# clock.net
KiCad netlist of a schematic drawn in EAGLE
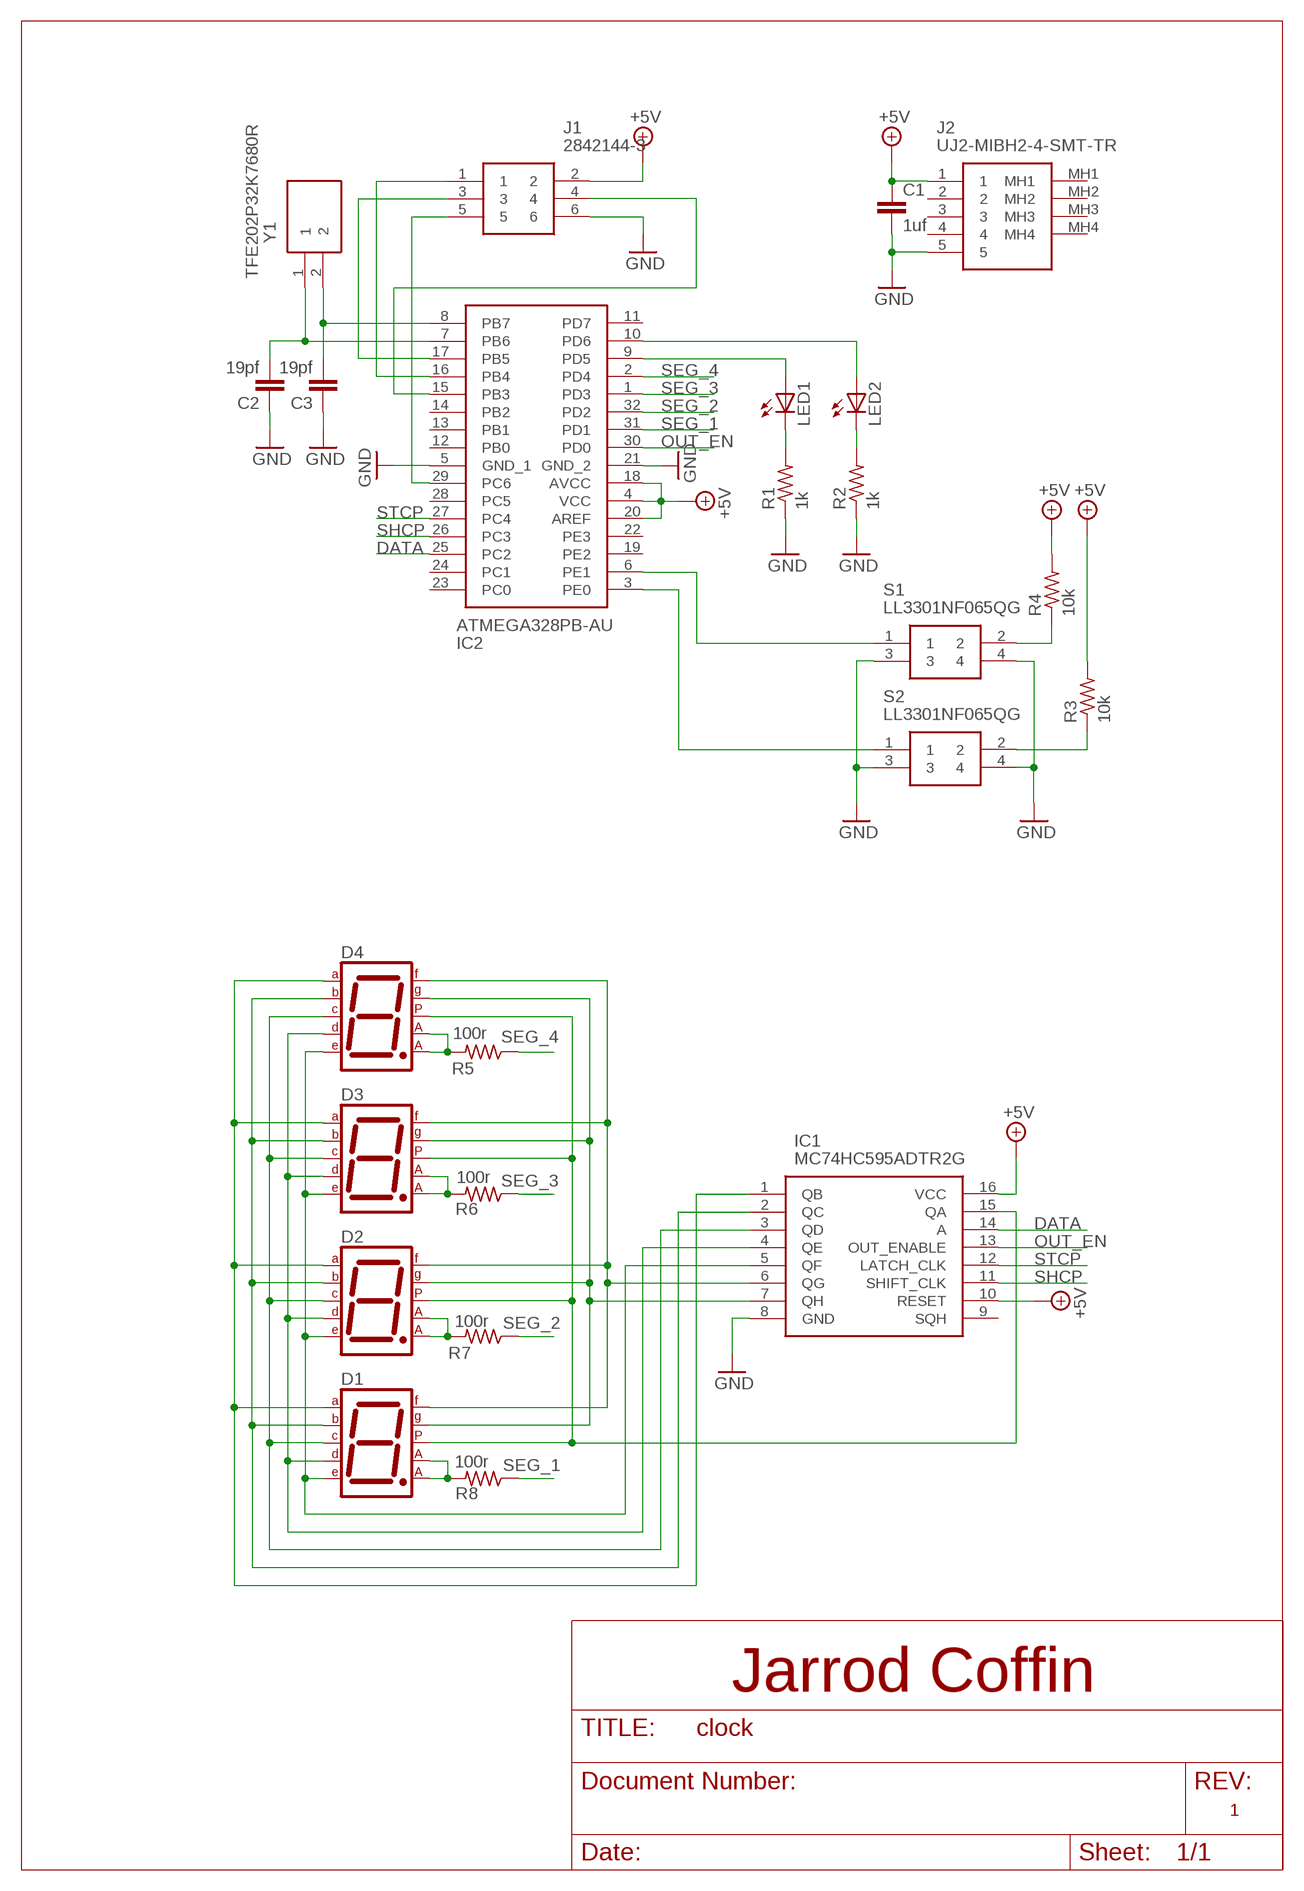
[diagram p0: schematic, sheet 1]

(export (version "E")
  (design (tool "Eeschema 10.0.6"))
  (components
    (comp (ref "C1")
      (value "1uf")
      (footprint "eagle-import:C0805")
      (libsource (lib "eagle-import") (part "C-EUC0805"))
    )
    (comp (ref "C2")
      (value "19pf")
      (footprint "eagle-import:C0603")
      (libsource (lib "eagle-import") (part "C-EUC0603"))
    )
    (comp (ref "C3")
      (value "19pf")
      (footprint "eagle-import:C0603")
      (libsource (lib "eagle-import") (part "C-EUC0603"))
    )
    (comp (ref "D1")
      (value "7SEG-CA")
      (footprint "eagle-import:7SEG-13")
      (libsource (lib "eagle-import") (part "7SEG-CA"))
    )
    (comp (ref "D2")
      (value "7SEG-CA")
      (footprint "eagle-import:7SEG-13")
      (libsource (lib "eagle-import") (part "7SEG-CA"))
    )
    (comp (ref "D3")
      (value "7SEG-CA")
      (footprint "eagle-import:7SEG-13")
      (libsource (lib "eagle-import") (part "7SEG-CA"))
    )
    (comp (ref "D4")
      (value "7SEG-CA")
      (footprint "eagle-import:7SEG-13")
      (libsource (lib "eagle-import") (part "7SEG-CA"))
    )
    (comp (ref "IC1")
      (value "MC74HC595ADTR2G")
      (footprint "eagle-import:SOP65P640X120-16N")
      (fields (field (name "MOUSER_PART_NUMBER") "863-MC74HC595ADTR2G"))
      (libsource (lib "eagle-import") (part "MC74HC595ADTR2G"))
    )
    (comp (ref "IC2")
      (value "ATMEGA328PB-AU")
      (footprint "eagle-import:QFP80P900X900X120-32N")
      (fields (field (name "MOUSER_PART_NUMBER") "556-ATMEGA328PB-AU"))
      (libsource (lib "eagle-import") (part "ATMEGA328PB-AU"))
    )
    (comp (ref "J1")
      (value "2842144-3")
      (footprint "eagle-import:HUSSP6W50P200_2X3_600X400X590P")
      (fields (field (name "MOUSER_PART_NUMBER") "571-2842144-3"))
      (libsource (lib "eagle-import") (part "2842144-3"))
    )
    (comp (ref "J2")
      (value "UJ2-MIBH2-4-SMT-TR")
      (footprint "eagle-import:UJ2MIBH24SMTTR")
      (fields (field (name "MOUSER_PART_NUMBER") "490-UJ2-MIBH2-4-SMT"))
      (libsource (lib "eagle-import") (part "UJ2-MIBH2-4-SMT-TR"))
    )
    (comp (ref "LED1")
      (value "LED3MM")
      (footprint "eagle-import:LED3MM")
      (libsource (lib "eagle-import") (part "LED3MM"))
    )
    (comp (ref "LED2")
      (value "LED3MM")
      (footprint "eagle-import:LED3MM")
      (libsource (lib "eagle-import") (part "LED3MM"))
    )
    (comp (ref "R1")
      (value "1k")
      (footprint "eagle-import:R0805")
      (libsource (lib "eagle-import") (part "R-US_R0805"))
    )
    (comp (ref "R2")
      (value "1k")
      (footprint "eagle-import:R0805")
      (libsource (lib "eagle-import") (part "R-US_R0805"))
    )
    (comp (ref "R3")
      (value "10k")
      (footprint "eagle-import:R0805")
      (libsource (lib "eagle-import") (part "R-US_R0805"))
    )
    (comp (ref "R4")
      (value "10k")
      (footprint "eagle-import:R0805")
      (libsource (lib "eagle-import") (part "R-US_R0805"))
    )
    (comp (ref "R5")
      (value "100r")
      (footprint "eagle-import:R0805")
      (libsource (lib "eagle-import") (part "R-US_R0805"))
    )
    (comp (ref "R6")
      (value "100r")
      (footprint "eagle-import:R0805")
      (libsource (lib "eagle-import") (part "R-US_R0805"))
    )
    (comp (ref "R7")
      (value "100r")
      (footprint "eagle-import:R0805")
      (libsource (lib "eagle-import") (part "R-US_R0805"))
    )
    (comp (ref "R8")
      (value "100r")
      (footprint "eagle-import:R0805")
      (libsource (lib "eagle-import") (part "R-US_R0805"))
    )
    (comp (ref "S1")
      (value "LL3301NF065QG")
      (footprint "eagle-import:LL3301NF065QG")
      (fields (field (name "MOUSER_PART_NUMBER") "612-LL3301NF065QG"))
      (libsource (lib "eagle-import") (part "LL3301NF065QG"))
    )
    (comp (ref "S2")
      (value "LL3301NF065QG")
      (footprint "eagle-import:LL3301NF065QG")
      (fields (field (name "MOUSER_PART_NUMBER") "612-LL3301NF065QG"))
      (libsource (lib "eagle-import") (part "LL3301NF065QG"))
    )
    (comp (ref "Y1")
      (value "TFE202P32K7680R")
      (footprint "eagle-import:TFE202P32K7680R")
      (fields (field (name "MOUSER_PART_NUMBER") "774-TFE202P32K7680R"))
      (libsource (lib "eagle-import") (part "TFE202P32K7680R"))
    )
  )
  (nets
    (net (code "1") (name "+5V") (class "Default")
      (node (ref "C1") (pin "1") (pinfunction "1_1") (pintype "passive"))
      (node (ref "IC1") (pin "10") (pinfunction "RESET_10") (pintype "bidirectional"))
      (node (ref "IC1") (pin "16") (pinfunction "VCC_16") (pintype "power_in"))
      (node (ref "IC2") (pin "18") (pinfunction "AVCC_18") (pintype "bidirectional"))
      (node (ref "IC2") (pin "20") (pinfunction "AREF_20") (pintype "bidirectional"))
      (node (ref "IC2") (pin "4") (pinfunction "VCC_4") (pintype "bidirectional"))
      (node (ref "J1") (pin "2") (pinfunction "2_2") (pintype "bidirectional"))
      (node (ref "J2") (pin "1") (pinfunction "1_1") (pintype "bidirectional"))
      (node (ref "R3") (pin "2") (pinfunction "2_2") (pintype "passive"))
      (node (ref "R4") (pin "2") (pinfunction "2_2") (pintype "passive"))
    )
    (net (code "2") (name "/DATA") (class "Default")
      (node (ref "IC1") (pin "14") (pinfunction "A_14") (pintype "bidirectional"))
      (node (ref "IC2") (pin "25") (pinfunction "PC2_25") (pintype "bidirectional"))
    )
    (net (code "3") (name "/OUT_EN") (class "Default")
      (node (ref "IC1") (pin "13") (pinfunction "OUT_ENABLE_13") (pintype "output"))
      (node (ref "IC2") (pin "30") (pinfunction "PD0_30") (pintype "bidirectional"))
    )
    (net (code "4") (name "/SEG_1") (class "Default")
      (node (ref "IC2") (pin "31") (pinfunction "PD1_31") (pintype "bidirectional"))
      (node (ref "R8") (pin "1") (pinfunction "1_1") (pintype "passive"))
    )
    (net (code "5") (name "/SEG_2") (class "Default")
      (node (ref "IC2") (pin "32") (pinfunction "PD2_32") (pintype "bidirectional"))
      (node (ref "R7") (pin "1") (pinfunction "1_1") (pintype "passive"))
    )
    (net (code "6") (name "/SEG_3") (class "Default")
      (node (ref "IC2") (pin "1") (pinfunction "PD3_1") (pintype "bidirectional"))
      (node (ref "R6") (pin "1") (pinfunction "1_1") (pintype "passive"))
    )
    (net (code "7") (name "/SEG_4") (class "Default")
      (node (ref "IC2") (pin "2") (pinfunction "PD4_2") (pintype "bidirectional"))
      (node (ref "R5") (pin "1") (pinfunction "1_1") (pintype "passive"))
    )
    (net (code "8") (name "/SHCP") (class "Default")
      (node (ref "IC1") (pin "11") (pinfunction "SHIFT_CLK_11") (pintype "input"))
      (node (ref "IC2") (pin "26") (pinfunction "PC3_26") (pintype "bidirectional"))
    )
    (net (code "9") (name "/STCP") (class "Default")
      (node (ref "IC1") (pin "12") (pinfunction "LATCH_CLK_12") (pintype "input"))
      (node (ref "IC2") (pin "27") (pinfunction "PC4_27") (pintype "bidirectional"))
    )
    (net (code "10") (name "GND") (class "Default")
      (node (ref "C1") (pin "2") (pinfunction "2_2") (pintype "passive"))
      (node (ref "C2") (pin "1") (pinfunction "1_1") (pintype "passive"))
      (node (ref "C3") (pin "1") (pinfunction "1_1") (pintype "passive"))
      (node (ref "IC1") (pin "8") (pinfunction "GND_8") (pintype "power_in"))
      (node (ref "IC2") (pin "21") (pinfunction "GND_2_21") (pintype "bidirectional"))
      (node (ref "IC2") (pin "5") (pinfunction "GND_1_5") (pintype "bidirectional"))
      (node (ref "J1") (pin "6") (pinfunction "6_6") (pintype "bidirectional"))
      (node (ref "J2") (pin "5") (pinfunction "5_5") (pintype "bidirectional"))
      (node (ref "R1") (pin "1") (pinfunction "1_1") (pintype "passive"))
      (node (ref "R2") (pin "1") (pinfunction "1_1") (pintype "passive"))
      (node (ref "S1") (pin "3") (pinfunction "3_3") (pintype "bidirectional"))
      (node (ref "S1") (pin "4") (pinfunction "4_4") (pintype "bidirectional"))
      (node (ref "S2") (pin "3") (pinfunction "3_3") (pintype "bidirectional"))
      (node (ref "S2") (pin "4") (pinfunction "4_4") (pintype "bidirectional"))
    )
    (net (code "11") (name "Net-(D1-A)") (class "Default")
      (node (ref "D1") (pin "7") (pinfunction "A_7") (pintype "passive"))
      (node (ref "D2") (pin "7") (pinfunction "A_7") (pintype "passive"))
      (node (ref "D3") (pin "7") (pinfunction "A_7") (pintype "passive"))
      (node (ref "D4") (pin "7") (pinfunction "A_7") (pintype "passive"))
      (node (ref "IC1") (pin "1") (pinfunction "QB_1") (pintype "bidirectional"))
    )
    (net (code "12") (name "Net-(D1-B)") (class "Default")
      (node (ref "D1") (pin "6") (pinfunction "B_6") (pintype "passive"))
      (node (ref "D2") (pin "6") (pinfunction "B_6") (pintype "passive"))
      (node (ref "D3") (pin "6") (pinfunction "B_6") (pintype "passive"))
      (node (ref "D4") (pin "6") (pinfunction "B_6") (pintype "passive"))
      (node (ref "IC1") (pin "2") (pinfunction "QC_2") (pintype "bidirectional"))
    )
    (net (code "13") (name "Net-(D1-C)") (class "Default")
      (node (ref "D1") (pin "4") (pinfunction "C_4") (pintype "passive"))
      (node (ref "D2") (pin "4") (pinfunction "C_4") (pintype "passive"))
      (node (ref "D3") (pin "4") (pinfunction "C_4") (pintype "passive"))
      (node (ref "D4") (pin "4") (pinfunction "C_4") (pintype "passive"))
      (node (ref "IC1") (pin "3") (pinfunction "QD_3") (pintype "bidirectional"))
    )
    (net (code "14") (name "Net-(D1-CA1)") (class "Default")
      (node (ref "D1") (pin "3") (pinfunction "CA1_3") (pintype "passive"))
      (node (ref "D1") (pin "8") (pinfunction "CA2_8") (pintype "passive"))
      (node (ref "R8") (pin "2") (pinfunction "2_2") (pintype "passive"))
    )
    (net (code "15") (name "Net-(D1-D)") (class "Default")
      (node (ref "D1") (pin "2") (pinfunction "D_2") (pintype "passive"))
      (node (ref "D2") (pin "2") (pinfunction "D_2") (pintype "passive"))
      (node (ref "D3") (pin "2") (pinfunction "D_2") (pintype "passive"))
      (node (ref "D4") (pin "2") (pinfunction "D_2") (pintype "passive"))
      (node (ref "IC1") (pin "4") (pinfunction "QE_4") (pintype "bidirectional"))
    )
    (net (code "16") (name "Net-(D1-DP)") (class "Default")
      (node (ref "D1") (pin "5") (pinfunction "DP_5") (pintype "passive"))
      (node (ref "D2") (pin "5") (pinfunction "DP_5") (pintype "passive"))
      (node (ref "D3") (pin "5") (pinfunction "DP_5") (pintype "passive"))
      (node (ref "D4") (pin "5") (pinfunction "DP_5") (pintype "passive"))
      (node (ref "IC1") (pin "15") (pinfunction "QA_15") (pintype "bidirectional"))
    )
    (net (code "17") (name "Net-(D1-E)") (class "Default")
      (node (ref "D1") (pin "1") (pinfunction "E_1") (pintype "passive"))
      (node (ref "D2") (pin "1") (pinfunction "E_1") (pintype "passive"))
      (node (ref "D3") (pin "1") (pinfunction "E_1") (pintype "passive"))
      (node (ref "D4") (pin "1") (pinfunction "E_1") (pintype "passive"))
      (node (ref "IC1") (pin "5") (pinfunction "QF_5") (pintype "bidirectional"))
    )
    (net (code "18") (name "Net-(D1-F)") (class "Default")
      (node (ref "D1") (pin "9") (pinfunction "F_9") (pintype "passive"))
      (node (ref "D2") (pin "9") (pinfunction "F_9") (pintype "passive"))
      (node (ref "D3") (pin "9") (pinfunction "F_9") (pintype "passive"))
      (node (ref "D4") (pin "9") (pinfunction "F_9") (pintype "passive"))
      (node (ref "IC1") (pin "6") (pinfunction "QG_6") (pintype "bidirectional"))
    )
    (net (code "19") (name "Net-(D1-G)") (class "Default")
      (node (ref "D1") (pin "10") (pinfunction "G_10") (pintype "passive"))
      (node (ref "D2") (pin "10") (pinfunction "G_10") (pintype "passive"))
      (node (ref "D3") (pin "10") (pinfunction "G_10") (pintype "passive"))
      (node (ref "D4") (pin "10") (pinfunction "G_10") (pintype "passive"))
      (node (ref "IC1") (pin "7") (pinfunction "QH_7") (pintype "bidirectional"))
    )
    (net (code "20") (name "Net-(D2-CA1)") (class "Default")
      (node (ref "D2") (pin "3") (pinfunction "CA1_3") (pintype "passive"))
      (node (ref "D2") (pin "8") (pinfunction "CA2_8") (pintype "passive"))
      (node (ref "R7") (pin "2") (pinfunction "2_2") (pintype "passive"))
    )
    (net (code "21") (name "Net-(D3-CA1)") (class "Default")
      (node (ref "D3") (pin "3") (pinfunction "CA1_3") (pintype "passive"))
      (node (ref "D3") (pin "8") (pinfunction "CA2_8") (pintype "passive"))
      (node (ref "R6") (pin "2") (pinfunction "2_2") (pintype "passive"))
    )
    (net (code "22") (name "Net-(D4-CA1)") (class "Default")
      (node (ref "D4") (pin "3") (pinfunction "CA1_3") (pintype "passive"))
      (node (ref "D4") (pin "8") (pinfunction "CA2_8") (pintype "passive"))
      (node (ref "R5") (pin "2") (pinfunction "2_2") (pintype "passive"))
    )
    (net (code "23") (name "Net-(IC2-PB3)") (class "Default")
      (node (ref "IC2") (pin "15") (pinfunction "PB3_15") (pintype "bidirectional"))
      (node (ref "J1") (pin "4") (pinfunction "4_4") (pintype "bidirectional"))
    )
    (net (code "24") (name "Net-(IC2-PB4)") (class "Default")
      (node (ref "IC2") (pin "16") (pinfunction "PB4_16") (pintype "bidirectional"))
      (node (ref "J1") (pin "1") (pinfunction "1_1") (pintype "bidirectional"))
    )
    (net (code "25") (name "Net-(IC2-PB5)") (class "Default")
      (node (ref "IC2") (pin "17") (pinfunction "PB5_17") (pintype "bidirectional"))
      (node (ref "J1") (pin "3") (pinfunction "3_3") (pintype "bidirectional"))
    )
    (net (code "26") (name "Net-(IC2-PB6)") (class "Default")
      (node (ref "C2") (pin "2") (pinfunction "2_2") (pintype "passive"))
      (node (ref "IC2") (pin "7") (pinfunction "PB6_7") (pintype "bidirectional"))
      (node (ref "Y1") (pin "1") (pinfunction "1_1") (pintype "bidirectional"))
    )
    (net (code "27") (name "Net-(IC2-PB7)") (class "Default")
      (node (ref "C3") (pin "2") (pinfunction "2_2") (pintype "passive"))
      (node (ref "IC2") (pin "8") (pinfunction "PB7_8") (pintype "bidirectional"))
      (node (ref "Y1") (pin "2") (pinfunction "2_2") (pintype "bidirectional"))
    )
    (net (code "28") (name "Net-(IC2-PC6)") (class "Default")
      (node (ref "IC2") (pin "29") (pinfunction "PC6_29") (pintype "bidirectional"))
      (node (ref "J1") (pin "5") (pinfunction "5_5") (pintype "bidirectional"))
    )
    (net (code "29") (name "Net-(IC2-PD5)") (class "Default")
      (node (ref "IC2") (pin "9") (pinfunction "PD5_9") (pintype "bidirectional"))
      (node (ref "LED1") (pin "A") (pinfunction "A_A") (pintype "passive"))
    )
    (net (code "30") (name "Net-(IC2-PD6)") (class "Default")
      (node (ref "IC2") (pin "10") (pinfunction "PD6_10") (pintype "bidirectional"))
      (node (ref "LED2") (pin "A") (pinfunction "A_A") (pintype "passive"))
    )
    (net (code "31") (name "Net-(IC2-PE0)") (class "Default")
      (node (ref "IC2") (pin "3") (pinfunction "PE0_3") (pintype "bidirectional"))
      (node (ref "S2") (pin "1") (pinfunction "1_1") (pintype "bidirectional"))
    )
    (net (code "32") (name "Net-(IC2-PE1)") (class "Default")
      (node (ref "IC2") (pin "6") (pinfunction "PE1_6") (pintype "bidirectional"))
      (node (ref "S1") (pin "1") (pinfunction "1_1") (pintype "bidirectional"))
    )
    (net (code "33") (name "Net-(LED1-C)") (class "Default")
      (node (ref "LED1") (pin "K") (pinfunction "C_K") (pintype "passive"))
      (node (ref "R1") (pin "2") (pinfunction "2_2") (pintype "passive"))
    )
    (net (code "34") (name "Net-(LED2-C)") (class "Default")
      (node (ref "LED2") (pin "K") (pinfunction "C_K") (pintype "passive"))
      (node (ref "R2") (pin "2") (pinfunction "2_2") (pintype "passive"))
    )
    (net (code "35") (name "Net-(R3-Pad1)") (class "Default")
      (node (ref "R3") (pin "1") (pinfunction "1_1") (pintype "passive"))
      (node (ref "S2") (pin "2") (pinfunction "2_2") (pintype "bidirectional"))
    )
    (net (code "36") (name "Net-(R4-Pad1)") (class "Default")
      (node (ref "R4") (pin "1") (pinfunction "1_1") (pintype "passive"))
      (node (ref "S1") (pin "2") (pinfunction "2_2") (pintype "bidirectional"))
    )
    (net (code "37") (name "unconnected-(IC1-SQH-Pad9)") (class "Default")
      (node (ref "IC1") (pin "9") (pinfunction "SQH_9") (pintype "bidirectional"))
    )
    (net (code "38") (name "unconnected-(IC2-PB0-Pad12)") (class "Default")
      (node (ref "IC2") (pin "12") (pinfunction "PB0_12") (pintype "bidirectional"))
    )
    (net (code "39") (name "unconnected-(IC2-PB1-Pad13)") (class "Default")
      (node (ref "IC2") (pin "13") (pinfunction "PB1_13") (pintype "bidirectional"))
    )
    (net (code "40") (name "unconnected-(IC2-PB2-Pad14)") (class "Default")
      (node (ref "IC2") (pin "14") (pinfunction "PB2_14") (pintype "bidirectional"))
    )
    (net (code "41") (name "unconnected-(IC2-PC0-Pad23)") (class "Default")
      (node (ref "IC2") (pin "23") (pinfunction "PC0_23") (pintype "bidirectional"))
    )
    (net (code "42") (name "unconnected-(IC2-PC1-Pad24)") (class "Default")
      (node (ref "IC2") (pin "24") (pinfunction "PC1_24") (pintype "bidirectional"))
    )
    (net (code "43") (name "unconnected-(IC2-PC5-Pad28)") (class "Default")
      (node (ref "IC2") (pin "28") (pinfunction "PC5_28") (pintype "bidirectional"))
    )
    (net (code "44") (name "unconnected-(IC2-PD7-Pad11)") (class "Default")
      (node (ref "IC2") (pin "11") (pinfunction "PD7_11") (pintype "bidirectional"))
    )
    (net (code "45") (name "unconnected-(IC2-PE2-Pad19)") (class "Default")
      (node (ref "IC2") (pin "19") (pinfunction "PE2_19") (pintype "bidirectional"))
    )
    (net (code "46") (name "unconnected-(IC2-PE3-Pad22)") (class "Default")
      (node (ref "IC2") (pin "22") (pinfunction "PE3_22") (pintype "bidirectional"))
    )
    (net (code "47") (name "unconnected-(J2-Pad2)") (class "Default")
      (node (ref "J2") (pin "2") (pinfunction "2_2") (pintype "bidirectional"))
    )
    (net (code "48") (name "unconnected-(J2-Pad3)") (class "Default")
      (node (ref "J2") (pin "3") (pinfunction "3_3") (pintype "bidirectional"))
    )
    (net (code "49") (name "unconnected-(J2-Pad4)") (class "Default")
      (node (ref "J2") (pin "4") (pinfunction "4_4") (pintype "bidirectional"))
    )
    (net (code "50") (name "unconnected-(J2-PadMH1)") (class "Default")
      (node (ref "J2") (pin "MH1") (pinfunction "MH1_MH1") (pintype "bidirectional"))
    )
    (net (code "51") (name "unconnected-(J2-PadMH2)") (class "Default")
      (node (ref "J2") (pin "MH2") (pinfunction "MH2_MH2") (pintype "bidirectional"))
    )
    (net (code "52") (name "unconnected-(J2-PadMH3)") (class "Default")
      (node (ref "J2") (pin "MH3") (pinfunction "MH3_MH3") (pintype "bidirectional"))
    )
    (net (code "53") (name "unconnected-(J2-PadMH4)") (class "Default")
      (node (ref "J2") (pin "MH4") (pinfunction "MH4_MH4") (pintype "bidirectional"))
    )
  )
)
